# side_panel_V5.net
KiCad netlist of a schematic drawn in EAGLE
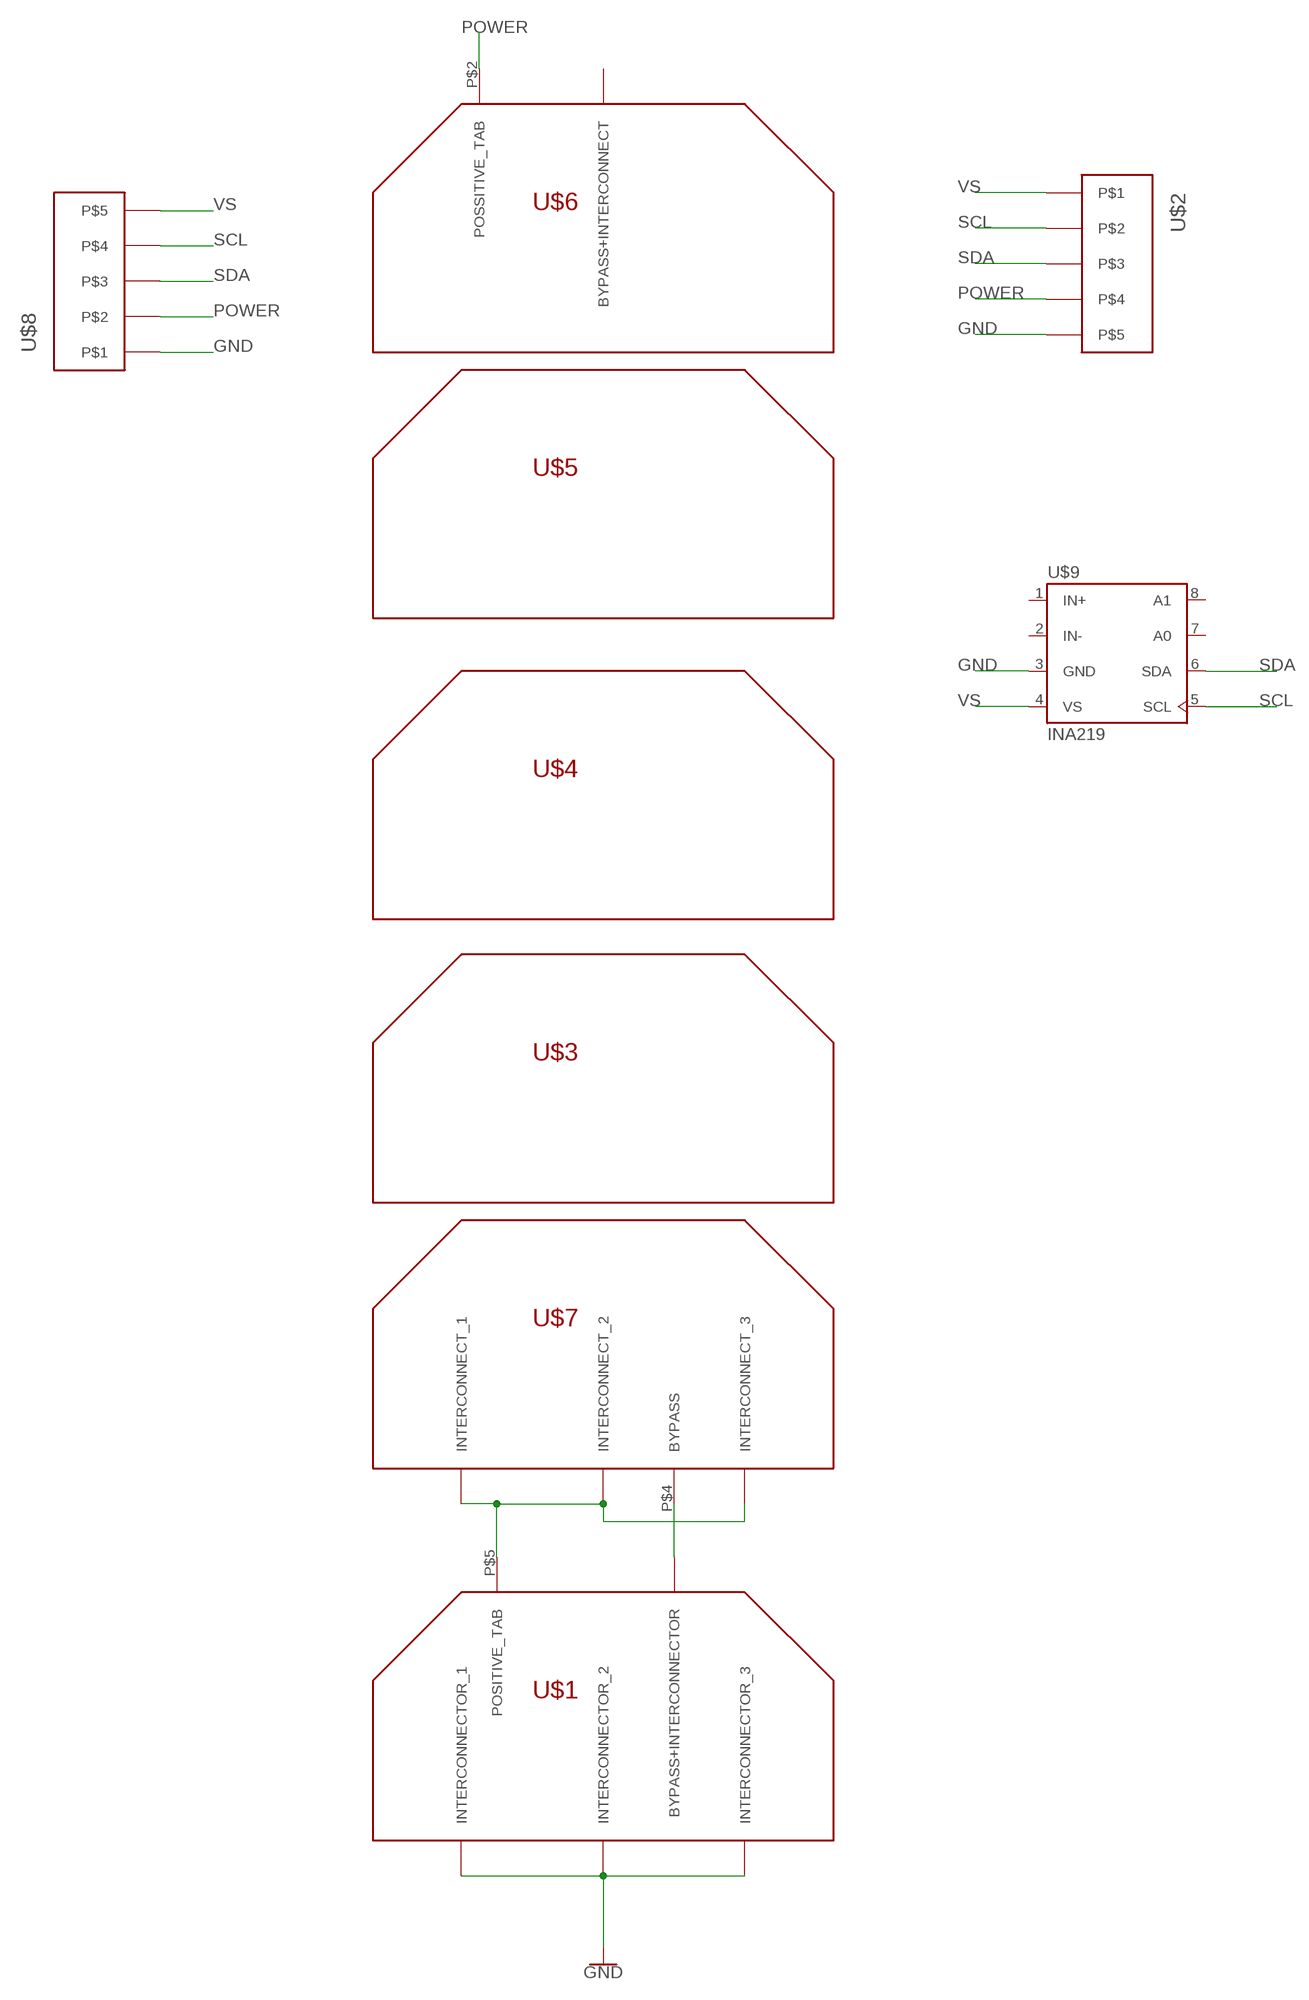
[diagram p0: schematic, sheet 1]

(export (version "E")
  (design (tool "Eeschema 10.0.6"))
  (components
    (comp (ref "U$1")
      (value "SOLAR_CELL_STAND-ALONE")
      (footprint "eagle-import:SOLAR_CELL_STAND-ALONE")
      (libsource (lib "eagle-import") (part "SOLAR_CELL_STAND-ALONE"))
    )
    (comp (ref "U$2")
      (value "PICOLOCK_5")
      (footprint "eagle-import:PICOLOCK_5")
      (libsource (lib "eagle-import") (part "PICOLOCK_5"))
    )
    (comp (ref "U$3")
      (value "SOALAR_CELL_OUTLINE")
      (footprint "eagle-import:SOLAR_CELL_OUTLINE")
      (libsource (lib "eagle-import") (part "SOALAR_CELL_OUTLINE"))
    )
    (comp (ref "U$4")
      (value "SOALAR_CELL_OUTLINE")
      (footprint "eagle-import:SOLAR_CELL_OUTLINE")
      (libsource (lib "eagle-import") (part "SOALAR_CELL_OUTLINE"))
    )
    (comp (ref "U$5")
      (value "SOALAR_CELL_OUTLINE")
      (footprint "eagle-import:SOLAR_CELL_OUTLINE")
      (libsource (lib "eagle-import") (part "SOALAR_CELL_OUTLINE"))
    )
    (comp (ref "U$6")
      (value "SOLAR_CELL_TOP")
      (footprint "eagle-import:SOLAR_CELL_TOP_SHORT-PAD")
      (libsource (lib "eagle-import") (part "SOLAR_CELL_TOP"))
    )
    (comp (ref "U$7")
      (value "SOLAR_CELL_BOTTOM+BYPASS")
      (footprint "eagle-import:SOLAR_CELL_BOTTOM+BYPASS")
      (libsource (lib "eagle-import") (part "SOLAR_CELL_BOTTOM+BYPASS"))
    )
    (comp (ref "U$8")
      (value "PICOLOCK_5")
      (footprint "eagle-import:PICOLOCK_5")
      (libsource (lib "eagle-import") (part "PICOLOCK_5"))
    )
    (comp (ref "U$9")
      (value "INA219")
      (footprint "eagle-import:S008")
      (libsource (lib "eagle-import") (part "INA219"))
    )
  )
  (nets
    (net (code "1") (name "/POWER") (class "Default")
      (node (ref "U$2") (pin "P$4") (pinfunction "P$4_P$4") (pintype "bidirectional"))
      (node (ref "U$6") (pin "P$2") (pinfunction "POSSITIVE_TAB_P$2") (pintype "bidirectional"))
      (node (ref "U$8") (pin "P$2") (pinfunction "P$2_P$2") (pintype "bidirectional"))
    )
    (net (code "2") (name "/SCL") (class "Default")
      (node (ref "U$2") (pin "P$2") (pinfunction "P$2_P$2") (pintype "bidirectional"))
      (node (ref "U$8") (pin "P$4") (pinfunction "P$4_P$4") (pintype "bidirectional"))
      (node (ref "U$9") (pin "5") (pinfunction "SCL_5") (pintype "input"))
    )
    (net (code "3") (name "/SDA") (class "Default")
      (node (ref "U$2") (pin "P$3") (pinfunction "P$3_P$3") (pintype "bidirectional"))
      (node (ref "U$8") (pin "P$3") (pinfunction "P$3_P$3") (pintype "bidirectional"))
      (node (ref "U$9") (pin "6") (pinfunction "SDA_6") (pintype "output"))
    )
    (net (code "4") (name "/VS") (class "Default")
      (node (ref "U$2") (pin "P$1") (pinfunction "P$1_P$1") (pintype "bidirectional"))
      (node (ref "U$8") (pin "P$5") (pinfunction "P$5_P$5") (pintype "bidirectional"))
      (node (ref "U$9") (pin "4") (pinfunction "VS_4") (pintype "power_in"))
    )
    (net (code "5") (name "GND") (class "Default")
      (node (ref "U$1") (pin "P$1") (pinfunction "INTERCONNECTOR_1_P$1") (pintype "bidirectional"))
      (node (ref "U$1") (pin "P$2") (pinfunction "INTERCONNECTOR_2_P$2") (pintype "bidirectional"))
      (node (ref "U$1") (pin "P$3") (pinfunction "INTERCONNECTOR_3_P$3") (pintype "bidirectional"))
      (node (ref "U$2") (pin "P$5") (pinfunction "P$5_P$5") (pintype "bidirectional"))
      (node (ref "U$8") (pin "P$1") (pinfunction "P$1_P$1") (pintype "bidirectional"))
      (node (ref "U$9") (pin "3") (pinfunction "GND_3") (pintype "power_in"))
    )
    (net (code "6") (name "Net-(U$1-BYPASS+INTERCONNECTOR)") (class "Default")
      (node (ref "U$1") (pin "P$4") (pinfunction "BYPASS+INTERCONNECTOR_P$4") (pintype "bidirectional"))
      (node (ref "U$7") (pin "P$4") (pinfunction "BYPASS_P$4") (pintype "bidirectional"))
    )
    (net (code "7") (name "Net-(U$1-POSITIVE_TAB)") (class "Default")
      (node (ref "U$1") (pin "P$5") (pinfunction "POSITIVE_TAB_P$5") (pintype "bidirectional"))
      (node (ref "U$7") (pin "P$1") (pinfunction "INTERCONNECT_1_P$1") (pintype "bidirectional"))
      (node (ref "U$7") (pin "P$2") (pinfunction "INTERCONNECT_2_P$2") (pintype "bidirectional"))
      (node (ref "U$7") (pin "P$3") (pinfunction "INTERCONNECT_3_P$3") (pintype "bidirectional"))
    )
    (net (code "8") (name "unconnected-(U$6-BYPASS+INTERCONNECT-PadP$1)") (class "Default")
      (node (ref "U$6") (pin "P$1") (pinfunction "BYPASS+INTERCONNECT_P$1") (pintype "bidirectional"))
    )
    (net (code "9") (name "unconnected-(U$9-A0-Pad7)") (class "Default")
      (node (ref "U$9") (pin "7") (pinfunction "A0_7") (pintype "input"))
    )
    (net (code "10") (name "unconnected-(U$9-A1-Pad8)") (class "Default")
      (node (ref "U$9") (pin "8") (pinfunction "A1_8") (pintype "input"))
    )
    (net (code "11") (name "unconnected-(U$9-IN+-Pad1)") (class "Default")
      (node (ref "U$9") (pin "1") (pinfunction "IN+_1") (pintype "input"))
    )
    (net (code "12") (name "unconnected-(U$9-IN--Pad2)") (class "Default")
      (node (ref "U$9") (pin "2") (pinfunction "IN-_2") (pintype "input"))
    )
  )
)
